# cv-board.net
KiCad netlist of a schematic drawn in EAGLE
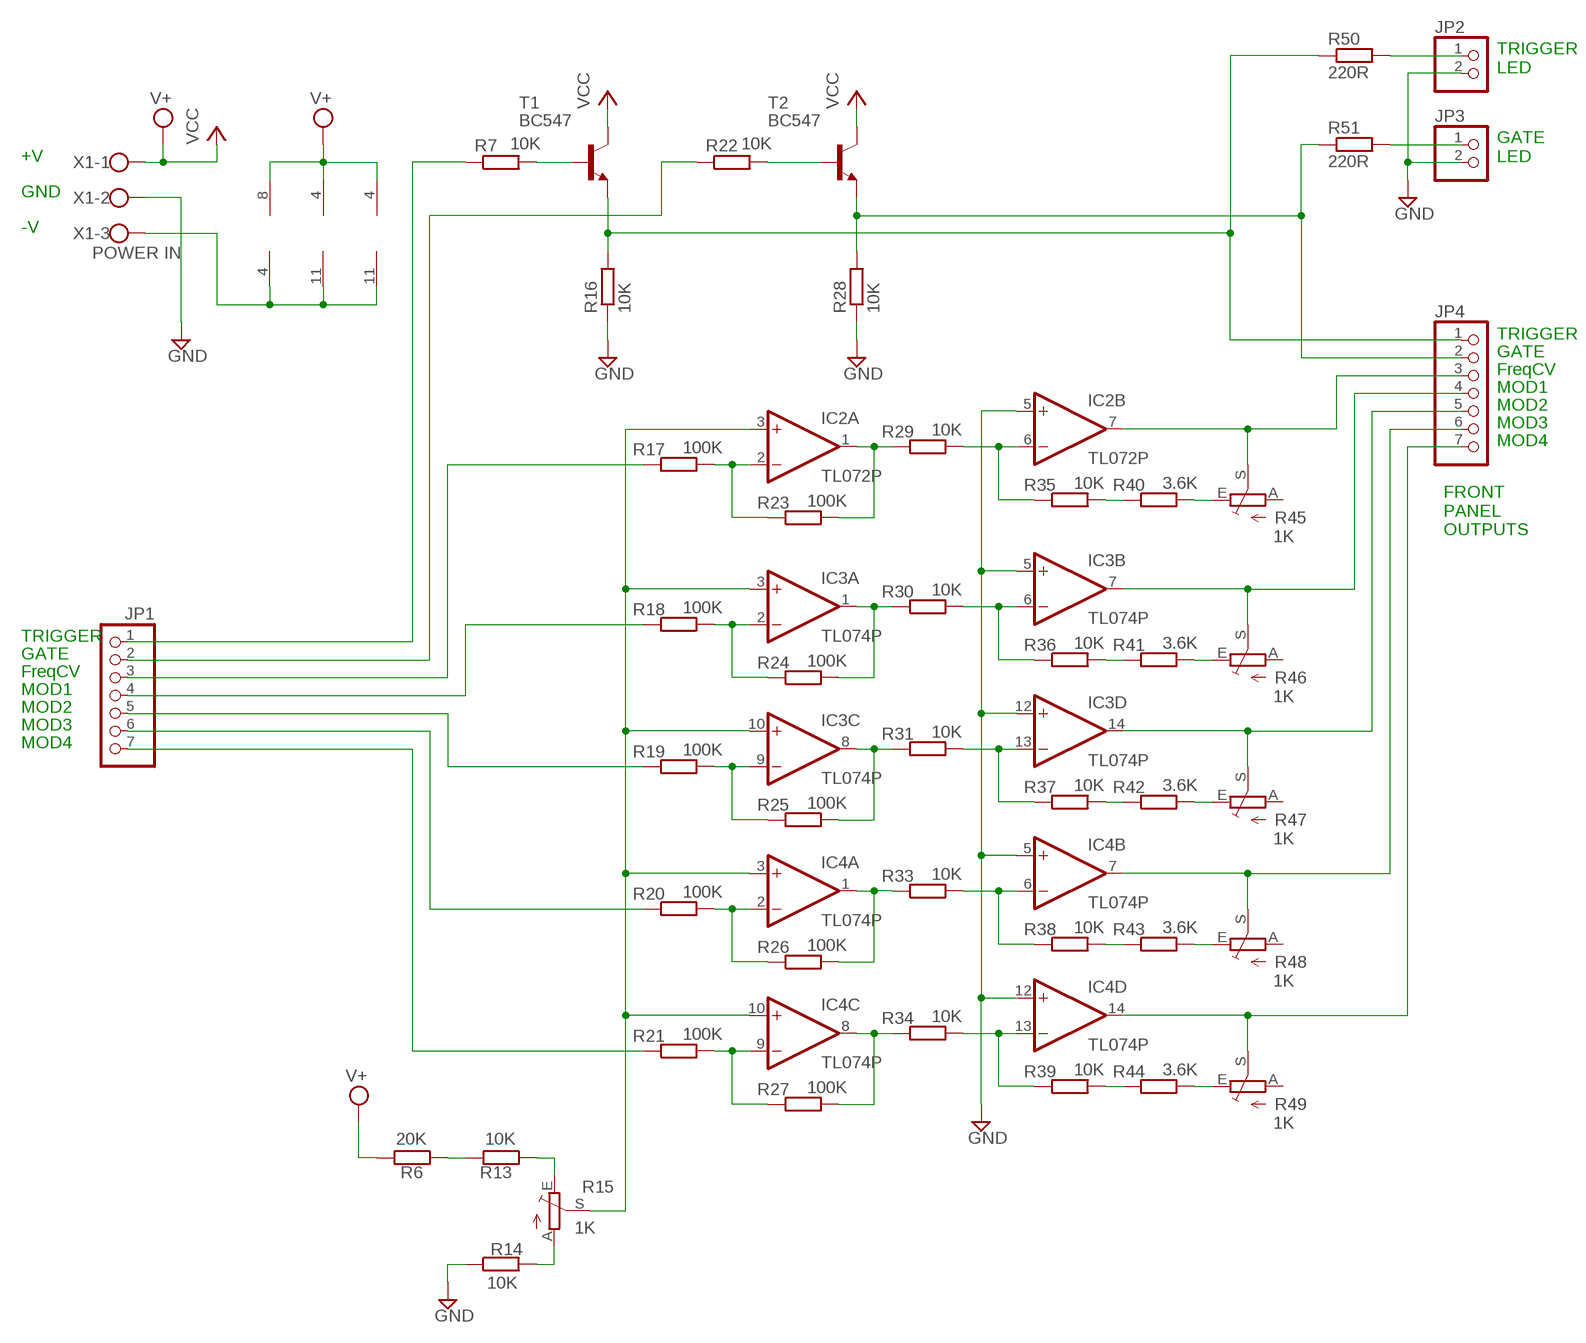
[diagram p0: schematic, sheet 1]

(export (version "E")
  (design (tool "Eeschema 10.0.6"))
  (components
    (comp (ref "IC2")
      (value "TL072P")
      (footprint "eagle-import:DIL08")
      (libsource (lib "eagle-import") (part "TL072P"))
    )
    (comp (ref "IC3")
      (value "TL074P")
      (footprint "eagle-import:DIL14")
      (libsource (lib "eagle-import") (part "TL074P"))
    )
    (comp (ref "IC4")
      (value "TL074P")
      (footprint "eagle-import:DIL14")
      (libsource (lib "eagle-import") (part "TL074P"))
    )
    (comp (ref "JP1")
      (value "PINHD-1X7")
      (footprint "eagle-import:1X07")
      (libsource (lib "eagle-import") (part "PINHD-1X7"))
    )
    (comp (ref "JP2")
      (value "PINHD-1X2")
      (footprint "eagle-import:1X02")
      (libsource (lib "eagle-import") (part "PINHD-1X2"))
    )
    (comp (ref "JP3")
      (value "PINHD-1X2")
      (footprint "eagle-import:1X02")
      (libsource (lib "eagle-import") (part "PINHD-1X2"))
    )
    (comp (ref "JP4")
      (value "PINHD-1X7")
      (footprint "eagle-import:1X07")
      (libsource (lib "eagle-import") (part "PINHD-1X7"))
    )
    (comp (ref "R6")
      (value "20K")
      (footprint "eagle-import:0207_7")
      (libsource (lib "eagle-import") (part "R-EU_0207/7"))
    )
    (comp (ref "R7")
      (value "10K")
      (footprint "eagle-import:0207_7")
      (libsource (lib "eagle-import") (part "R-EU_0207/7"))
    )
    (comp (ref "R13")
      (value "10K")
      (footprint "eagle-import:0207_7")
      (libsource (lib "eagle-import") (part "R-EU_0207/7"))
    )
    (comp (ref "R14")
      (value "10K")
      (footprint "eagle-import:0207_7")
      (libsource (lib "eagle-import") (part "R-EU_0207/7"))
    )
    (comp (ref "R15")
      (value "1K")
      (footprint "eagle-import:CA6V")
      (libsource (lib "eagle-import") (part "TRIM_EU-CA6V"))
    )
    (comp (ref "R16")
      (value "10K")
      (footprint "eagle-import:0207_7")
      (libsource (lib "eagle-import") (part "R-EU_0207/7"))
    )
    (comp (ref "R17")
      (value "100K")
      (footprint "eagle-import:0207_7")
      (libsource (lib "eagle-import") (part "R-EU_0207/7"))
    )
    (comp (ref "R18")
      (value "100K")
      (footprint "eagle-import:0207_7")
      (libsource (lib "eagle-import") (part "R-EU_0207/7"))
    )
    (comp (ref "R19")
      (value "100K")
      (footprint "eagle-import:0207_7")
      (libsource (lib "eagle-import") (part "R-EU_0207/7"))
    )
    (comp (ref "R20")
      (value "100K")
      (footprint "eagle-import:0207_7")
      (libsource (lib "eagle-import") (part "R-EU_0207/7"))
    )
    (comp (ref "R21")
      (value "100K")
      (footprint "eagle-import:0207_7")
      (libsource (lib "eagle-import") (part "R-EU_0207/7"))
    )
    (comp (ref "R22")
      (value "10K")
      (footprint "eagle-import:0207_7")
      (libsource (lib "eagle-import") (part "R-EU_0207/7"))
    )
    (comp (ref "R23")
      (value "100K")
      (footprint "eagle-import:0207_7")
      (libsource (lib "eagle-import") (part "R-EU_0207/7"))
    )
    (comp (ref "R24")
      (value "100K")
      (footprint "eagle-import:0207_7")
      (libsource (lib "eagle-import") (part "R-EU_0207/7"))
    )
    (comp (ref "R25")
      (value "100K")
      (footprint "eagle-import:0207_7")
      (libsource (lib "eagle-import") (part "R-EU_0207/7"))
    )
    (comp (ref "R26")
      (value "100K")
      (footprint "eagle-import:0207_7")
      (libsource (lib "eagle-import") (part "R-EU_0207/7"))
    )
    (comp (ref "R27")
      (value "100K")
      (footprint "eagle-import:0207_7")
      (libsource (lib "eagle-import") (part "R-EU_0207/7"))
    )
    (comp (ref "R28")
      (value "10K")
      (footprint "eagle-import:0207_7")
      (libsource (lib "eagle-import") (part "R-EU_0207/7"))
    )
    (comp (ref "R29")
      (value "10K")
      (footprint "eagle-import:0207_7")
      (libsource (lib "eagle-import") (part "R-EU_0207/7"))
    )
    (comp (ref "R30")
      (value "10K")
      (footprint "eagle-import:0207_7")
      (libsource (lib "eagle-import") (part "R-EU_0207/7"))
    )
    (comp (ref "R31")
      (value "10K")
      (footprint "eagle-import:0207_7")
      (libsource (lib "eagle-import") (part "R-EU_0207/7"))
    )
    (comp (ref "R33")
      (value "10K")
      (footprint "eagle-import:0207_7")
      (libsource (lib "eagle-import") (part "R-EU_0207/7"))
    )
    (comp (ref "R34")
      (value "10K")
      (footprint "eagle-import:0207_7")
      (libsource (lib "eagle-import") (part "R-EU_0207/7"))
    )
    (comp (ref "R35")
      (value "10K")
      (footprint "eagle-import:0207_7")
      (libsource (lib "eagle-import") (part "R-EU_0207/7"))
    )
    (comp (ref "R36")
      (value "10K")
      (footprint "eagle-import:0207_7")
      (libsource (lib "eagle-import") (part "R-EU_0207/7"))
    )
    (comp (ref "R37")
      (value "10K")
      (footprint "eagle-import:0207_7")
      (libsource (lib "eagle-import") (part "R-EU_0207/7"))
    )
    (comp (ref "R38")
      (value "10K")
      (footprint "eagle-import:0207_7")
      (libsource (lib "eagle-import") (part "R-EU_0207/7"))
    )
    (comp (ref "R39")
      (value "10K")
      (footprint "eagle-import:0207_7")
      (libsource (lib "eagle-import") (part "R-EU_0207/7"))
    )
    (comp (ref "R40")
      (value "3.6K")
      (footprint "eagle-import:0207_7")
      (libsource (lib "eagle-import") (part "R-EU_0207/7"))
    )
    (comp (ref "R41")
      (value "3.6K")
      (footprint "eagle-import:0207_7")
      (libsource (lib "eagle-import") (part "R-EU_0207/7"))
    )
    (comp (ref "R42")
      (value "3.6K")
      (footprint "eagle-import:0207_7")
      (libsource (lib "eagle-import") (part "R-EU_0207/7"))
    )
    (comp (ref "R43")
      (value "3.6K")
      (footprint "eagle-import:0207_7")
      (libsource (lib "eagle-import") (part "R-EU_0207/7"))
    )
    (comp (ref "R44")
      (value "3.6K")
      (footprint "eagle-import:0207_7")
      (libsource (lib "eagle-import") (part "R-EU_0207/7"))
    )
    (comp (ref "R45")
      (value "1K")
      (footprint "eagle-import:CA6V")
      (libsource (lib "eagle-import") (part "TRIM_EU-CA6V"))
    )
    (comp (ref "R46")
      (value "1K")
      (footprint "eagle-import:CA6V")
      (libsource (lib "eagle-import") (part "TRIM_EU-CA6V"))
    )
    (comp (ref "R47")
      (value "1K")
      (footprint "eagle-import:CA6V")
      (libsource (lib "eagle-import") (part "TRIM_EU-CA6V"))
    )
    (comp (ref "R48")
      (value "1K")
      (footprint "eagle-import:CA6V")
      (libsource (lib "eagle-import") (part "TRIM_EU-CA6V"))
    )
    (comp (ref "R49")
      (value "1K")
      (footprint "eagle-import:CA6V")
      (libsource (lib "eagle-import") (part "TRIM_EU-CA6V"))
    )
    (comp (ref "R50")
      (value "220R")
      (footprint "eagle-import:0207_7")
      (libsource (lib "eagle-import") (part "R-EU_0207/7"))
    )
    (comp (ref "R51")
      (value "220R")
      (footprint "eagle-import:0207_7")
      (libsource (lib "eagle-import") (part "R-EU_0207/7"))
    )
    (comp (ref "T1")
      (value "BC547")
      (footprint "eagle-import:TO92")
      (libsource (lib "eagle-import") (part "BC547"))
    )
    (comp (ref "T2")
      (value "BC547")
      (footprint "eagle-import:TO92")
      (libsource (lib "eagle-import") (part "BC547"))
    )
    (comp (ref "X1")
      (value "POWER IN")
      (footprint "eagle-import:W237-103")
      (fields (field (name "MPN") "237-103"))
      (libsource (lib "eagle-import") (part "W237-103"))
    )
  )
  (nets
    (net (code "1") (name "GND") (class "Default")
      (node (ref "IC2") (pin "5") (pinfunction "+IN_5") (pintype "input"))
      (node (ref "IC3") (pin "12") (pinfunction "+IN_12") (pintype "input"))
      (node (ref "IC3") (pin "5") (pinfunction "+IN_5") (pintype "input"))
      (node (ref "IC4") (pin "12") (pinfunction "+IN_12") (pintype "input"))
      (node (ref "IC4") (pin "5") (pinfunction "+IN_5") (pintype "input"))
      (node (ref "JP2") (pin "2") (pinfunction "2_2") (pintype "passive"))
      (node (ref "JP3") (pin "2") (pinfunction "2_2") (pintype "passive"))
      (node (ref "R14") (pin "1") (pinfunction "1_1") (pintype "passive"))
      (node (ref "R16") (pin "1") (pinfunction "1_1") (pintype "passive"))
      (node (ref "R28") (pin "1") (pinfunction "1_1") (pintype "passive"))
      (node (ref "X1") (pin "2") (pinfunction "KL_2") (pintype "passive"))
    )
    (net (code "2") (name "Net-(IC2A-+IN)") (class "Default")
      (node (ref "IC2") (pin "3") (pinfunction "+IN_3") (pintype "input"))
      (node (ref "IC3") (pin "10") (pinfunction "+IN_10") (pintype "input"))
      (node (ref "IC3") (pin "3") (pinfunction "+IN_3") (pintype "input"))
      (node (ref "IC4") (pin "10") (pinfunction "+IN_10") (pintype "input"))
      (node (ref "IC4") (pin "3") (pinfunction "+IN_3") (pintype "input"))
      (node (ref "R15") (pin "S") (pinfunction "S_S") (pintype "passive"))
    )
    (net (code "3") (name "Net-(IC2A--IN)") (class "Default")
      (node (ref "IC2") (pin "2") (pinfunction "-IN_2") (pintype "input"))
      (node (ref "R17") (pin "2") (pinfunction "2_2") (pintype "passive"))
      (node (ref "R23") (pin "1") (pinfunction "1_1") (pintype "passive"))
    )
    (net (code "4") (name "Net-(IC2A-OUT)") (class "Default")
      (node (ref "IC2") (pin "1") (pinfunction "OUT_1") (pintype "output"))
      (node (ref "R23") (pin "2") (pinfunction "2_2") (pintype "passive"))
      (node (ref "R29") (pin "1") (pinfunction "1_1") (pintype "passive"))
    )
    (net (code "5") (name "Net-(IC2B--IN)") (class "Default")
      (node (ref "IC2") (pin "6") (pinfunction "-IN_6") (pintype "input"))
      (node (ref "R29") (pin "2") (pinfunction "2_2") (pintype "passive"))
      (node (ref "R35") (pin "1") (pinfunction "1_1") (pintype "passive"))
    )
    (net (code "6") (name "Net-(IC2B-OUT)") (class "Default")
      (node (ref "IC2") (pin "7") (pinfunction "OUT_7") (pintype "output"))
      (node (ref "JP4") (pin "3") (pinfunction "3_3") (pintype "passive"))
      (node (ref "R45") (pin "S") (pinfunction "S_S") (pintype "passive"))
    )
    (net (code "7") (name "Net-(IC2C-V-)") (class "Default")
      (node (ref "IC2") (pin "4") (pinfunction "V-_4") (pintype "power_in"))
      (node (ref "IC3") (pin "11") (pinfunction "V-_11") (pintype "power_in"))
      (node (ref "IC4") (pin "11") (pinfunction "V-_11") (pintype "power_in"))
      (node (ref "X1") (pin "3") (pinfunction "KL_3") (pintype "passive"))
    )
    (net (code "8") (name "Net-(IC3A--IN)") (class "Default")
      (node (ref "IC3") (pin "2") (pinfunction "-IN_2") (pintype "input"))
      (node (ref "R18") (pin "2") (pinfunction "2_2") (pintype "passive"))
      (node (ref "R24") (pin "1") (pinfunction "1_1") (pintype "passive"))
    )
    (net (code "9") (name "Net-(IC3A-OUT)") (class "Default")
      (node (ref "IC3") (pin "1") (pinfunction "OUT_1") (pintype "output"))
      (node (ref "R24") (pin "2") (pinfunction "2_2") (pintype "passive"))
      (node (ref "R30") (pin "1") (pinfunction "1_1") (pintype "passive"))
    )
    (net (code "10") (name "Net-(IC3B--IN)") (class "Default")
      (node (ref "IC3") (pin "6") (pinfunction "-IN_6") (pintype "input"))
      (node (ref "R30") (pin "2") (pinfunction "2_2") (pintype "passive"))
      (node (ref "R36") (pin "1") (pinfunction "1_1") (pintype "passive"))
    )
    (net (code "11") (name "Net-(IC3B-OUT)") (class "Default")
      (node (ref "IC3") (pin "7") (pinfunction "OUT_7") (pintype "output"))
      (node (ref "JP4") (pin "4") (pinfunction "4_4") (pintype "passive"))
      (node (ref "R46") (pin "S") (pinfunction "S_S") (pintype "passive"))
    )
    (net (code "12") (name "Net-(IC3C--IN)") (class "Default")
      (node (ref "IC3") (pin "9") (pinfunction "-IN_9") (pintype "input"))
      (node (ref "R19") (pin "2") (pinfunction "2_2") (pintype "passive"))
      (node (ref "R25") (pin "1") (pinfunction "1_1") (pintype "passive"))
    )
    (net (code "13") (name "Net-(IC3C-OUT)") (class "Default")
      (node (ref "IC3") (pin "8") (pinfunction "OUT_8") (pintype "output"))
      (node (ref "R25") (pin "2") (pinfunction "2_2") (pintype "passive"))
      (node (ref "R31") (pin "1") (pinfunction "1_1") (pintype "passive"))
    )
    (net (code "14") (name "Net-(IC3D--IN)") (class "Default")
      (node (ref "IC3") (pin "13") (pinfunction "-IN_13") (pintype "input"))
      (node (ref "R31") (pin "2") (pinfunction "2_2") (pintype "passive"))
      (node (ref "R37") (pin "1") (pinfunction "1_1") (pintype "passive"))
    )
    (net (code "15") (name "Net-(IC3D-OUT)") (class "Default")
      (node (ref "IC3") (pin "14") (pinfunction "OUT_14") (pintype "output"))
      (node (ref "JP4") (pin "5") (pinfunction "5_5") (pintype "passive"))
      (node (ref "R47") (pin "S") (pinfunction "S_S") (pintype "passive"))
    )
    (net (code "16") (name "Net-(IC4A--IN)") (class "Default")
      (node (ref "IC4") (pin "2") (pinfunction "-IN_2") (pintype "input"))
      (node (ref "R20") (pin "2") (pinfunction "2_2") (pintype "passive"))
      (node (ref "R26") (pin "1") (pinfunction "1_1") (pintype "passive"))
    )
    (net (code "17") (name "Net-(IC4A-OUT)") (class "Default")
      (node (ref "IC4") (pin "1") (pinfunction "OUT_1") (pintype "output"))
      (node (ref "R26") (pin "2") (pinfunction "2_2") (pintype "passive"))
      (node (ref "R33") (pin "1") (pinfunction "1_1") (pintype "passive"))
    )
    (net (code "18") (name "Net-(IC4B--IN)") (class "Default")
      (node (ref "IC4") (pin "6") (pinfunction "-IN_6") (pintype "input"))
      (node (ref "R33") (pin "2") (pinfunction "2_2") (pintype "passive"))
      (node (ref "R38") (pin "1") (pinfunction "1_1") (pintype "passive"))
    )
    (net (code "19") (name "Net-(IC4B-OUT)") (class "Default")
      (node (ref "IC4") (pin "7") (pinfunction "OUT_7") (pintype "output"))
      (node (ref "JP4") (pin "6") (pinfunction "6_6") (pintype "passive"))
      (node (ref "R48") (pin "S") (pinfunction "S_S") (pintype "passive"))
    )
    (net (code "20") (name "Net-(IC4C--IN)") (class "Default")
      (node (ref "IC4") (pin "9") (pinfunction "-IN_9") (pintype "input"))
      (node (ref "R21") (pin "2") (pinfunction "2_2") (pintype "passive"))
      (node (ref "R27") (pin "1") (pinfunction "1_1") (pintype "passive"))
    )
    (net (code "21") (name "Net-(IC4C-OUT)") (class "Default")
      (node (ref "IC4") (pin "8") (pinfunction "OUT_8") (pintype "output"))
      (node (ref "R27") (pin "2") (pinfunction "2_2") (pintype "passive"))
      (node (ref "R34") (pin "1") (pinfunction "1_1") (pintype "passive"))
    )
    (net (code "22") (name "Net-(IC4D--IN)") (class "Default")
      (node (ref "IC4") (pin "13") (pinfunction "-IN_13") (pintype "input"))
      (node (ref "R34") (pin "2") (pinfunction "2_2") (pintype "passive"))
      (node (ref "R39") (pin "1") (pinfunction "1_1") (pintype "passive"))
    )
    (net (code "23") (name "Net-(IC4D-OUT)") (class "Default")
      (node (ref "IC4") (pin "14") (pinfunction "OUT_14") (pintype "output"))
      (node (ref "JP4") (pin "7") (pinfunction "7_7") (pintype "passive"))
      (node (ref "R49") (pin "S") (pinfunction "S_S") (pintype "passive"))
    )
    (net (code "24") (name "Net-(JP1-Pad1)") (class "Default")
      (node (ref "JP1") (pin "1") (pinfunction "1_1") (pintype "passive"))
      (node (ref "R7") (pin "1") (pinfunction "1_1") (pintype "passive"))
    )
    (net (code "25") (name "Net-(JP1-Pad2)") (class "Default")
      (node (ref "JP1") (pin "2") (pinfunction "2_2") (pintype "passive"))
      (node (ref "R22") (pin "1") (pinfunction "1_1") (pintype "passive"))
    )
    (net (code "26") (name "Net-(JP1-Pad3)") (class "Default")
      (node (ref "JP1") (pin "3") (pinfunction "3_3") (pintype "passive"))
      (node (ref "R17") (pin "1") (pinfunction "1_1") (pintype "passive"))
    )
    (net (code "27") (name "Net-(JP1-Pad4)") (class "Default")
      (node (ref "JP1") (pin "4") (pinfunction "4_4") (pintype "passive"))
      (node (ref "R18") (pin "1") (pinfunction "1_1") (pintype "passive"))
    )
    (net (code "28") (name "Net-(JP1-Pad5)") (class "Default")
      (node (ref "JP1") (pin "5") (pinfunction "5_5") (pintype "passive"))
      (node (ref "R19") (pin "1") (pinfunction "1_1") (pintype "passive"))
    )
    (net (code "29") (name "Net-(JP1-Pad6)") (class "Default")
      (node (ref "JP1") (pin "6") (pinfunction "6_6") (pintype "passive"))
      (node (ref "R20") (pin "1") (pinfunction "1_1") (pintype "passive"))
    )
    (net (code "30") (name "Net-(JP1-Pad7)") (class "Default")
      (node (ref "JP1") (pin "7") (pinfunction "7_7") (pintype "passive"))
      (node (ref "R21") (pin "1") (pinfunction "1_1") (pintype "passive"))
    )
    (net (code "31") (name "Net-(JP2-Pad1)") (class "Default")
      (node (ref "JP2") (pin "1") (pinfunction "1_1") (pintype "passive"))
      (node (ref "R50") (pin "2") (pinfunction "2_2") (pintype "passive"))
    )
    (net (code "32") (name "Net-(JP3-Pad1)") (class "Default")
      (node (ref "JP3") (pin "1") (pinfunction "1_1") (pintype "passive"))
      (node (ref "R51") (pin "2") (pinfunction "2_2") (pintype "passive"))
    )
    (net (code "33") (name "Net-(R13-Pad1)") (class "Default")
      (node (ref "R13") (pin "1") (pinfunction "1_1") (pintype "passive"))
      (node (ref "R15") (pin "E") (pinfunction "E_E") (pintype "passive"))
    )
    (net (code "34") (name "Net-(R13-Pad2)") (class "Default")
      (node (ref "R13") (pin "2") (pinfunction "2_2") (pintype "passive"))
      (node (ref "R6") (pin "1") (pinfunction "1_1") (pintype "passive"))
    )
    (net (code "35") (name "Net-(R14-Pad2)") (class "Default")
      (node (ref "R14") (pin "2") (pinfunction "2_2") (pintype "passive"))
      (node (ref "R15") (pin "A") (pinfunction "A_A") (pintype "passive"))
    )
    (net (code "36") (name "Net-(R35-Pad2)") (class "Default")
      (node (ref "R35") (pin "2") (pinfunction "2_2") (pintype "passive"))
      (node (ref "R40") (pin "1") (pinfunction "1_1") (pintype "passive"))
    )
    (net (code "37") (name "Net-(R36-Pad2)") (class "Default")
      (node (ref "R36") (pin "2") (pinfunction "2_2") (pintype "passive"))
      (node (ref "R41") (pin "1") (pinfunction "1_1") (pintype "passive"))
    )
    (net (code "38") (name "Net-(R37-Pad2)") (class "Default")
      (node (ref "R37") (pin "2") (pinfunction "2_2") (pintype "passive"))
      (node (ref "R42") (pin "1") (pinfunction "1_1") (pintype "passive"))
    )
    (net (code "39") (name "Net-(R38-Pad2)") (class "Default")
      (node (ref "R38") (pin "2") (pinfunction "2_2") (pintype "passive"))
      (node (ref "R43") (pin "1") (pinfunction "1_1") (pintype "passive"))
    )
    (net (code "40") (name "Net-(R39-Pad2)") (class "Default")
      (node (ref "R39") (pin "2") (pinfunction "2_2") (pintype "passive"))
      (node (ref "R44") (pin "1") (pinfunction "1_1") (pintype "passive"))
    )
    (net (code "41") (name "Net-(R40-Pad2)") (class "Default")
      (node (ref "R40") (pin "2") (pinfunction "2_2") (pintype "passive"))
      (node (ref "R45") (pin "E") (pinfunction "E_E") (pintype "passive"))
    )
    (net (code "42") (name "Net-(R41-Pad2)") (class "Default")
      (node (ref "R41") (pin "2") (pinfunction "2_2") (pintype "passive"))
      (node (ref "R46") (pin "E") (pinfunction "E_E") (pintype "passive"))
    )
    (net (code "43") (name "Net-(R42-Pad2)") (class "Default")
      (node (ref "R42") (pin "2") (pinfunction "2_2") (pintype "passive"))
      (node (ref "R47") (pin "E") (pinfunction "E_E") (pintype "passive"))
    )
    (net (code "44") (name "Net-(R43-Pad2)") (class "Default")
      (node (ref "R43") (pin "2") (pinfunction "2_2") (pintype "passive"))
      (node (ref "R48") (pin "E") (pinfunction "E_E") (pintype "passive"))
    )
    (net (code "45") (name "Net-(R44-Pad2)") (class "Default")
      (node (ref "R44") (pin "2") (pinfunction "2_2") (pintype "passive"))
      (node (ref "R49") (pin "E") (pinfunction "E_E") (pintype "passive"))
    )
    (net (code "46") (name "Net-(T1-B)") (class "Default")
      (node (ref "R7") (pin "2") (pinfunction "2_2") (pintype "passive"))
      (node (ref "T1") (pin "2") (pinfunction "B_2") (pintype "passive"))
    )
    (net (code "47") (name "Net-(T1-E)") (class "Default")
      (node (ref "JP4") (pin "1") (pinfunction "1_1") (pintype "passive"))
      (node (ref "R16") (pin "2") (pinfunction "2_2") (pintype "passive"))
      (node (ref "R50") (pin "1") (pinfunction "1_1") (pintype "passive"))
      (node (ref "T1") (pin "1") (pinfunction "E_1") (pintype "passive"))
    )
    (net (code "48") (name "Net-(T2-B)") (class "Default")
      (node (ref "R22") (pin "2") (pinfunction "2_2") (pintype "passive"))
      (node (ref "T2") (pin "2") (pinfunction "B_2") (pintype "passive"))
    )
    (net (code "49") (name "Net-(T2-E)") (class "Default")
      (node (ref "JP4") (pin "2") (pinfunction "2_2") (pintype "passive"))
      (node (ref "R28") (pin "2") (pinfunction "2_2") (pintype "passive"))
      (node (ref "R51") (pin "1") (pinfunction "1_1") (pintype "passive"))
      (node (ref "T2") (pin "1") (pinfunction "E_1") (pintype "passive"))
    )
    (net (code "50") (name "V+") (class "Default")
      (node (ref "IC2") (pin "8") (pinfunction "V+_8") (pintype "power_in"))
      (node (ref "IC3") (pin "4") (pinfunction "V+_4") (pintype "power_in"))
      (node (ref "IC4") (pin "4") (pinfunction "V+_4") (pintype "power_in"))
      (node (ref "R6") (pin "2") (pinfunction "2_2") (pintype "passive"))
      (node (ref "T1") (pin "3") (pinfunction "C_3") (pintype "passive"))
      (node (ref "T2") (pin "3") (pinfunction "C_3") (pintype "passive"))
      (node (ref "X1") (pin "1") (pinfunction "KL_1") (pintype "passive"))
    )
    (net (code "51") (name "unconnected-(R45-PadA)") (class "Default")
      (node (ref "R45") (pin "A") (pinfunction "A_A") (pintype "passive"))
    )
    (net (code "52") (name "unconnected-(R46-PadA)") (class "Default")
      (node (ref "R46") (pin "A") (pinfunction "A_A") (pintype "passive"))
    )
    (net (code "53") (name "unconnected-(R47-PadA)") (class "Default")
      (node (ref "R47") (pin "A") (pinfunction "A_A") (pintype "passive"))
    )
    (net (code "54") (name "unconnected-(R48-PadA)") (class "Default")
      (node (ref "R48") (pin "A") (pinfunction "A_A") (pintype "passive"))
    )
    (net (code "55") (name "unconnected-(R49-PadA)") (class "Default")
      (node (ref "R49") (pin "A") (pinfunction "A_A") (pintype "passive"))
    )
  )
)
